# ZTK7628P_convert_board_v1_0.net
KiCad netlist of a schematic drawn in Altium Designer
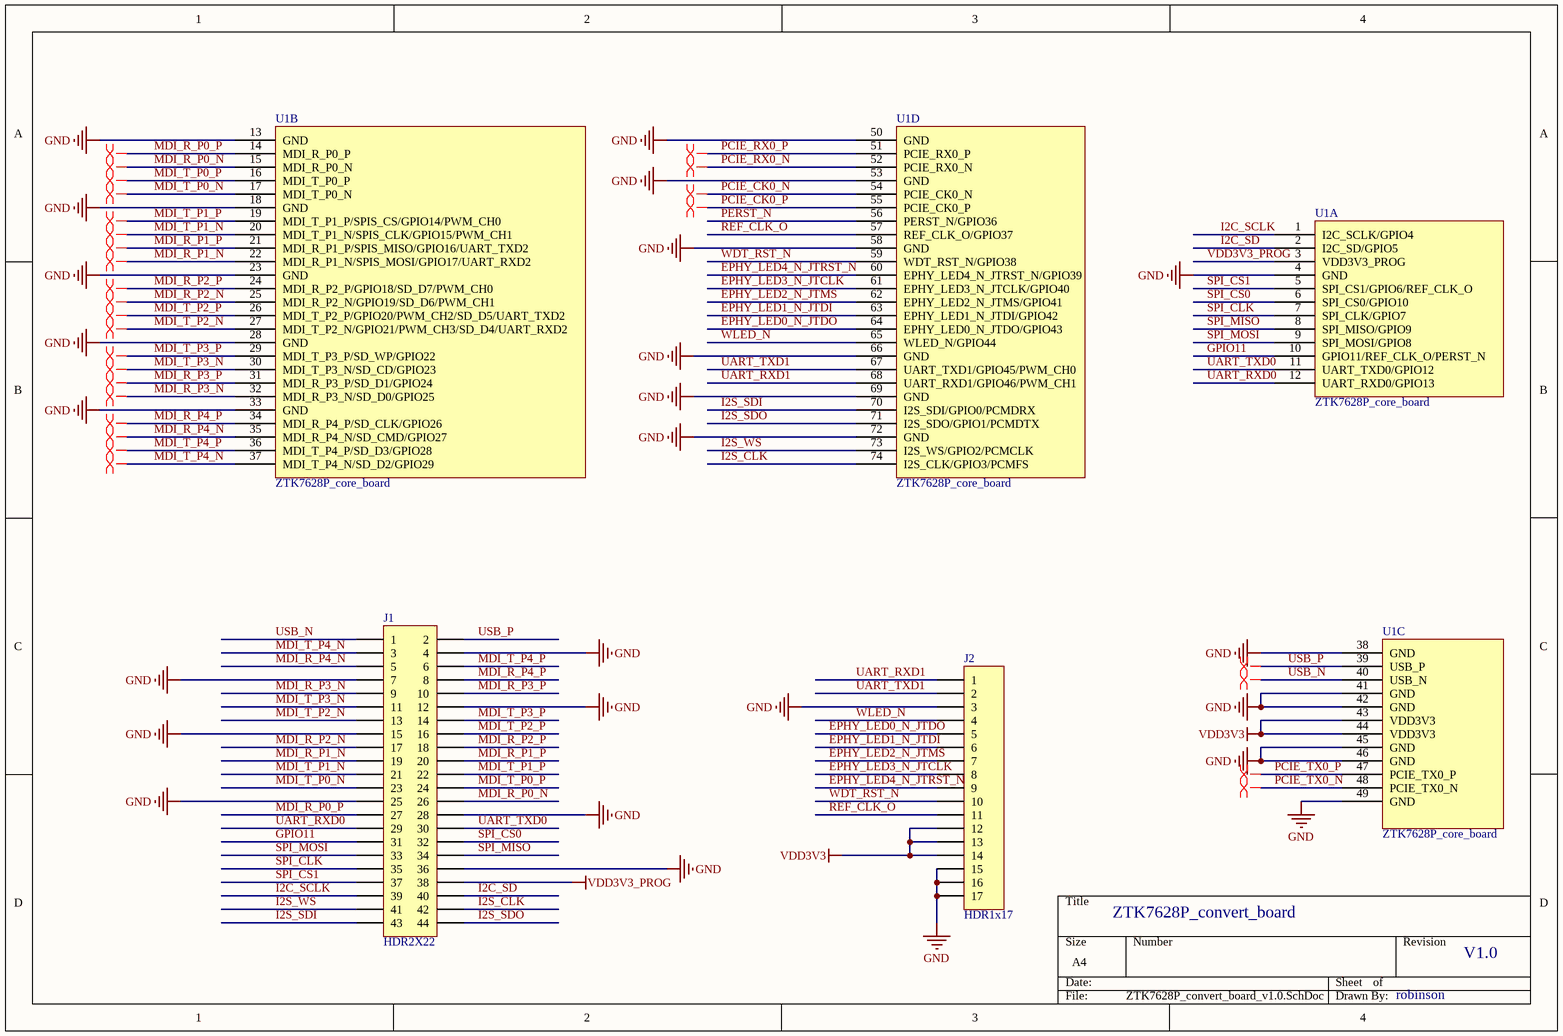
[diagram p0: ZTK7628P_convert_board_v1.0.SchDoc]

(export (version "E")
  (design (tool "Eeschema 10.0.6"))
  (components
    (comp (ref "J1")
      (value "HDR2X22")
      (footprint "MyMiscellaneousConnector:HDR2x22-P-2.0mm")
      (libsource (lib "MyMiscellaneousConnector") (part "HDR2X22"))
    )
    (comp (ref "J2")
      (value "HDR1x17")
      (footprint "MyMiscellaneousConnector:HDR1x17-P-2.0mm")
      (libsource (lib "MyMiscellaneousConnector") (part "HDR1x17"))
    )
    (comp (ref "U1")
      (value "ZTK7628P_core_board")
      (footprint "ZTK7628P_core_board")
      (libsource (lib "MyMiscellaneousDevice") (part "ZTK7628P_core_board"))
    )
  )
  (nets
    (net (code "1") (name "/EPHY_LED0_N_JTDO") (class "Default")
      (node (ref "J2") (pin "5") (pinfunction "5_5") (pintype "passive"))
      (node (ref "U1") (pin "64") (pinfunction "EPHY_LED0_N_JTDO/GPIO43_64") (pintype "passive"))
    )
    (net (code "2") (name "/EPHY_LED1_N_JTDI") (class "Default")
      (node (ref "J2") (pin "6") (pinfunction "6_6") (pintype "passive"))
      (node (ref "U1") (pin "63") (pinfunction "EPHY_LED1_N_JTDI/GPIO42_63") (pintype "passive"))
    )
    (net (code "3") (name "/EPHY_LED2_N_JTMS") (class "Default")
      (node (ref "J2") (pin "7") (pinfunction "7_7") (pintype "passive"))
      (node (ref "U1") (pin "62") (pinfunction "EPHY_LED2_N_JTMS/GPIO41_62") (pintype "passive"))
    )
    (net (code "4") (name "/EPHY_LED3_N_JTCLK") (class "Default")
      (node (ref "J2") (pin "8") (pinfunction "8_8") (pintype "passive"))
      (node (ref "U1") (pin "61") (pinfunction "EPHY_LED3_N_JTCLK/GPIO40_61") (pintype "passive"))
    )
    (net (code "5") (name "/EPHY_LED4_N_JTRST_N") (class "Default")
      (node (ref "J2") (pin "9") (pinfunction "9_9") (pintype "passive"))
      (node (ref "U1") (pin "60") (pinfunction "EPHY_LED4_N_JTRST_N/GPIO39_60") (pintype "passive"))
    )
    (net (code "6") (name "/GPIO11") (class "Default")
      (node (ref "J1") (pin "31") (pinfunction "31_31") (pintype "passive"))
      (node (ref "U1") (pin "10") (pinfunction "GPIO11/REF_CLK_O/PERST_N_10") (pintype "passive"))
    )
    (net (code "7") (name "/I2C_SCLK") (class "Default")
      (node (ref "J1") (pin "39") (pinfunction "39_39") (pintype "passive"))
      (node (ref "U1") (pin "1") (pinfunction "I2C_SCLK/GPIO4_1") (pintype "passive"))
    )
    (net (code "8") (name "/I2C_SD") (class "Default")
      (node (ref "J1") (pin "40") (pinfunction "40_40") (pintype "passive"))
      (node (ref "U1") (pin "2") (pinfunction "I2C_SD/GPIO5_2") (pintype "passive"))
    )
    (net (code "9") (name "/I2S_CLK") (class "Default")
      (node (ref "J1") (pin "42") (pinfunction "42_42") (pintype "passive"))
      (node (ref "U1") (pin "74") (pinfunction "I2S_CLK/GPIO3/PCMFS_74") (pintype "passive"))
    )
    (net (code "10") (name "/I2S_SDI") (class "Default")
      (node (ref "J1") (pin "43") (pinfunction "43_43") (pintype "passive"))
      (node (ref "U1") (pin "70") (pinfunction "I2S_SDI/GPIO0/PCMDRX_70") (pintype "passive"))
    )
    (net (code "11") (name "/I2S_SDO") (class "Default")
      (node (ref "J1") (pin "44") (pinfunction "44_44") (pintype "passive"))
      (node (ref "U1") (pin "71") (pinfunction "I2S_SDO/GPIO1/PCMDTX_71") (pintype "passive"))
    )
    (net (code "12") (name "/I2S_WS") (class "Default")
      (node (ref "J1") (pin "41") (pinfunction "41_41") (pintype "passive"))
      (node (ref "U1") (pin "73") (pinfunction "I2S_WS/GPIO2/PCMCLK_73") (pintype "passive"))
    )
    (net (code "13") (name "/MDI_R_P0_N") (class "Default")
      (node (ref "J1") (pin "26") (pinfunction "26_26") (pintype "passive"))
      (node (ref "U1") (pin "15") (pinfunction "MDI_R_P0_N_15") (pintype "passive"))
    )
    (net (code "14") (name "/MDI_R_P0_P") (class "Default")
      (node (ref "J1") (pin "27") (pinfunction "27_27") (pintype "passive"))
      (node (ref "U1") (pin "14") (pinfunction "MDI_R_P0_P_14") (pintype "passive"))
    )
    (net (code "15") (name "/MDI_R_P1_N") (class "Default")
      (node (ref "J1") (pin "19") (pinfunction "19_19") (pintype "passive"))
      (node (ref "U1") (pin "22") (pinfunction "MDI_R_P1_N/SPIS_MOSI/GPIO17/UART_RXD2_22") (pintype "passive"))
    )
    (net (code "16") (name "/MDI_R_P1_P") (class "Default")
      (node (ref "J1") (pin "20") (pinfunction "20_20") (pintype "passive"))
      (node (ref "U1") (pin "21") (pinfunction "MDI_R_P1_P/SPIS_MISO/GPIO16/UART_TXD2_21") (pintype "passive"))
    )
    (net (code "17") (name "/MDI_R_P2_N") (class "Default")
      (node (ref "J1") (pin "17") (pinfunction "17_17") (pintype "passive"))
      (node (ref "U1") (pin "25") (pinfunction "MDI_R_P2_N/GPIO19/SD_D6/PWM_CH1_25") (pintype "passive"))
    )
    (net (code "18") (name "/MDI_R_P2_P") (class "Default")
      (node (ref "J1") (pin "18") (pinfunction "18_18") (pintype "passive"))
      (node (ref "U1") (pin "24") (pinfunction "MDI_R_P2_P/GPIO18/SD_D7/PWM_CH0_24") (pintype "passive"))
    )
    (net (code "19") (name "/MDI_R_P3_N") (class "Default")
      (node (ref "J1") (pin "9") (pinfunction "9_9") (pintype "passive"))
      (node (ref "U1") (pin "32") (pinfunction "MDI_R_P3_N/SD_D0/GPIO25_32") (pintype "passive"))
    )
    (net (code "20") (name "/MDI_R_P3_P") (class "Default")
      (node (ref "J1") (pin "10") (pinfunction "10_10") (pintype "passive"))
      (node (ref "U1") (pin "31") (pinfunction "MDI_R_P3_P/SD_D1/GPIO24_31") (pintype "passive"))
    )
    (net (code "21") (name "/MDI_R_P4_N") (class "Default")
      (node (ref "J1") (pin "5") (pinfunction "5_5") (pintype "passive"))
      (node (ref "U1") (pin "35") (pinfunction "MDI_R_P4_N/SD_CMD/GPIO27_35") (pintype "passive"))
    )
    (net (code "22") (name "/MDI_R_P4_P") (class "Default")
      (node (ref "J1") (pin "8") (pinfunction "8_8") (pintype "passive"))
      (node (ref "U1") (pin "34") (pinfunction "MDI_R_P4_P/SD_CLK/GPIO26_34") (pintype "passive"))
    )
    (net (code "23") (name "/MDI_T_P0_N") (class "Default")
      (node (ref "J1") (pin "23") (pinfunction "23_23") (pintype "passive"))
      (node (ref "U1") (pin "17") (pinfunction "MDI_T_P0_N_17") (pintype "passive"))
    )
    (net (code "24") (name "/MDI_T_P0_P") (class "Default")
      (node (ref "J1") (pin "24") (pinfunction "24_24") (pintype "passive"))
      (node (ref "U1") (pin "16") (pinfunction "MDI_T_P0_P_16") (pintype "passive"))
    )
    (net (code "25") (name "/MDI_T_P1_N") (class "Default")
      (node (ref "J1") (pin "21") (pinfunction "21_21") (pintype "passive"))
      (node (ref "U1") (pin "20") (pinfunction "MDI_T_P1_N/SPIS_CLK/GPIO15/PWM_CH1_20") (pintype "passive"))
    )
    (net (code "26") (name "/MDI_T_P1_P") (class "Default")
      (node (ref "J1") (pin "22") (pinfunction "22_22") (pintype "passive"))
      (node (ref "U1") (pin "19") (pinfunction "MDI_T_P1_P/SPIS_CS/GPIO14/PWM_CH0_19") (pintype "passive"))
    )
    (net (code "27") (name "/MDI_T_P2_N") (class "Default")
      (node (ref "J1") (pin "13") (pinfunction "13_13") (pintype "passive"))
      (node (ref "U1") (pin "27") (pinfunction "MDI_T_P2_N/GPIO21/PWM_CH3/SD_D4/UART_RXD2_27") (pintype "passive"))
    )
    (net (code "28") (name "/MDI_T_P2_P") (class "Default")
      (node (ref "J1") (pin "16") (pinfunction "16_16") (pintype "passive"))
      (node (ref "U1") (pin "26") (pinfunction "MDI_T_P2_P/GPIO20/PWM_CH2/SD_D5/UART_TXD2_26") (pintype "passive"))
    )
    (net (code "29") (name "/MDI_T_P3_N") (class "Default")
      (node (ref "J1") (pin "11") (pinfunction "11_11") (pintype "passive"))
      (node (ref "U1") (pin "30") (pinfunction "MDI_T_P3_N/SD_CD/GPIO23_30") (pintype "passive"))
    )
    (net (code "30") (name "/MDI_T_P3_P") (class "Default")
      (node (ref "J1") (pin "14") (pinfunction "14_14") (pintype "passive"))
      (node (ref "U1") (pin "29") (pinfunction "MDI_T_P3_P/SD_WP/GPIO22_29") (pintype "passive"))
    )
    (net (code "31") (name "/MDI_T_P4_N") (class "Default")
      (node (ref "J1") (pin "3") (pinfunction "3_3") (pintype "passive"))
      (node (ref "U1") (pin "37") (pinfunction "MDI_T_P4_N/SD_D2/GPIO29_37") (pintype "passive"))
    )
    (net (code "32") (name "/MDI_T_P4_P") (class "Default")
      (node (ref "J1") (pin "6") (pinfunction "6_6") (pintype "passive"))
      (node (ref "U1") (pin "36") (pinfunction "MDI_T_P4_P/SD_D3/GPIO28_36") (pintype "passive"))
    )
    (net (code "33") (name "/PCIE_CK0_N") (class "Default")
      (node (ref "U1") (pin "54") (pinfunction "PCIE_CK0_N_54") (pintype "passive"))
    )
    (net (code "34") (name "/PCIE_CK0_P") (class "Default")
      (node (ref "U1") (pin "55") (pinfunction "PCIE_CK0_P_55") (pintype "passive"))
    )
    (net (code "35") (name "/PCIE_RX0_N") (class "Default")
      (node (ref "U1") (pin "52") (pinfunction "PCIE_RX0_N_52") (pintype "passive"))
    )
    (net (code "36") (name "/PCIE_RX0_P") (class "Default")
      (node (ref "U1") (pin "51") (pinfunction "PCIE_RX0_P_51") (pintype "passive"))
    )
    (net (code "37") (name "/PCIE_TX0_N") (class "Default")
      (node (ref "U1") (pin "48") (pinfunction "PCIE_TX0_N_48") (pintype "passive"))
    )
    (net (code "38") (name "/PCIE_TX0_P") (class "Default")
      (node (ref "U1") (pin "47") (pinfunction "PCIE_TX0_P_47") (pintype "passive"))
    )
    (net (code "39") (name "/PERST_N") (class "Default")
      (node (ref "U1") (pin "56") (pinfunction "PERST_N/GPIO36_56") (pintype "passive"))
    )
    (net (code "40") (name "/REF_CLK_O") (class "Default")
      (node (ref "J2") (pin "11") (pinfunction "11_11") (pintype "passive"))
      (node (ref "U1") (pin "57") (pinfunction "REF_CLK_O/GPIO37_57") (pintype "passive"))
    )
    (net (code "41") (name "/SPI_CLK") (class "Default")
      (node (ref "J1") (pin "35") (pinfunction "35_35") (pintype "passive"))
      (node (ref "U1") (pin "7") (pinfunction "SPI_CLK/GPIO7_7") (pintype "passive"))
    )
    (net (code "42") (name "/SPI_CS0") (class "Default")
      (node (ref "J1") (pin "32") (pinfunction "32_32") (pintype "passive"))
      (node (ref "U1") (pin "6") (pinfunction "SPI_CS0/GPIO10_6") (pintype "passive"))
    )
    (net (code "43") (name "/SPI_CS1") (class "Default")
      (node (ref "J1") (pin "37") (pinfunction "37_37") (pintype "passive"))
      (node (ref "U1") (pin "5") (pinfunction "SPI_CS1/GPIO6/REF_CLK_O_5") (pintype "passive"))
    )
    (net (code "44") (name "/SPI_MISO") (class "Default")
      (node (ref "J1") (pin "34") (pinfunction "34_34") (pintype "passive"))
      (node (ref "U1") (pin "8") (pinfunction "SPI_MISO/GPIO9_8") (pintype "passive"))
    )
    (net (code "45") (name "/SPI_MOSI") (class "Default")
      (node (ref "J1") (pin "33") (pinfunction "33_33") (pintype "passive"))
      (node (ref "U1") (pin "9") (pinfunction "SPI_MOSI/GPIO8_9") (pintype "passive"))
    )
    (net (code "46") (name "/UART_RXD0") (class "Default")
      (node (ref "J1") (pin "29") (pinfunction "29_29") (pintype "passive"))
      (node (ref "U1") (pin "12") (pinfunction "UART_RXD0/GPIO13_12") (pintype "passive"))
    )
    (net (code "47") (name "/UART_RXD1") (class "Default")
      (node (ref "J2") (pin "1") (pinfunction "1_1") (pintype "passive"))
      (node (ref "U1") (pin "68") (pinfunction "UART_RXD1/GPIO46/PWM_CH1_68") (pintype "passive"))
    )
    (net (code "48") (name "/UART_TXD0") (class "Default")
      (node (ref "J1") (pin "30") (pinfunction "30_30") (pintype "passive"))
      (node (ref "U1") (pin "11") (pinfunction "UART_TXD0/GPIO12_11") (pintype "passive"))
    )
    (net (code "49") (name "/UART_TXD1") (class "Default")
      (node (ref "J2") (pin "2") (pinfunction "2_2") (pintype "passive"))
      (node (ref "U1") (pin "67") (pinfunction "UART_TXD1/GPIO45/PWM_CH0_67") (pintype "passive"))
    )
    (net (code "50") (name "/USB_N") (class "Default")
      (node (ref "J1") (pin "1") (pinfunction "1_1") (pintype "passive"))
      (node (ref "U1") (pin "40") (pinfunction "USB_N_40") (pintype "passive"))
    )
    (net (code "51") (name "/USB_P") (class "Default")
      (node (ref "J1") (pin "2") (pinfunction "2_2") (pintype "passive"))
      (node (ref "U1") (pin "39") (pinfunction "USB_P_39") (pintype "passive"))
    )
    (net (code "52") (name "/WDT_RST_N") (class "Default")
      (node (ref "J2") (pin "10") (pinfunction "10_10") (pintype "passive"))
      (node (ref "U1") (pin "59") (pinfunction "WDT_RST_N/GPIO38_59") (pintype "passive"))
    )
    (net (code "53") (name "/WLED_N") (class "Default")
      (node (ref "J2") (pin "4") (pinfunction "4_4") (pintype "passive"))
      (node (ref "U1") (pin "65") (pinfunction "WLED_N/GPIO44_65") (pintype "passive"))
    )
    (net (code "54") (name "GND") (class "Default")
      (node (ref "J1") (pin "12") (pinfunction "12_12") (pintype "passive"))
      (node (ref "J1") (pin "15") (pinfunction "15_15") (pintype "passive"))
      (node (ref "J1") (pin "25") (pinfunction "25_25") (pintype "passive"))
      (node (ref "J1") (pin "28") (pinfunction "28_28") (pintype "passive"))
      (node (ref "J1") (pin "36") (pinfunction "36_36") (pintype "passive"))
      (node (ref "J1") (pin "4") (pinfunction "4_4") (pintype "passive"))
      (node (ref "J1") (pin "7") (pinfunction "7_7") (pintype "passive"))
      (node (ref "J2") (pin "15") (pinfunction "15_15") (pintype "passive"))
      (node (ref "J2") (pin "16") (pinfunction "16_16") (pintype "passive"))
      (node (ref "J2") (pin "17") (pinfunction "17_17") (pintype "passive"))
      (node (ref "J2") (pin "3") (pinfunction "3_3") (pintype "passive"))
      (node (ref "U1") (pin "13") (pinfunction "GND_13") (pintype "passive"))
      (node (ref "U1") (pin "18") (pinfunction "GND_18") (pintype "passive"))
      (node (ref "U1") (pin "23") (pinfunction "GND_23") (pintype "passive"))
      (node (ref "U1") (pin "28") (pinfunction "GND_28") (pintype "passive"))
      (node (ref "U1") (pin "33") (pinfunction "GND_33") (pintype "passive"))
      (node (ref "U1") (pin "38") (pinfunction "GND_38") (pintype "passive"))
      (node (ref "U1") (pin "4") (pinfunction "GND_4") (pintype "passive"))
      (node (ref "U1") (pin "41") (pinfunction "GND_41") (pintype "passive"))
      (node (ref "U1") (pin "42") (pinfunction "GND_42") (pintype "passive"))
      (node (ref "U1") (pin "45") (pinfunction "GND_45") (pintype "passive"))
      (node (ref "U1") (pin "46") (pinfunction "GND_46") (pintype "passive"))
      (node (ref "U1") (pin "49") (pinfunction "GND_49") (pintype "passive"))
      (node (ref "U1") (pin "50") (pinfunction "GND_50") (pintype "passive"))
      (node (ref "U1") (pin "53") (pinfunction "GND_53") (pintype "passive"))
      (node (ref "U1") (pin "58") (pinfunction "GND_58") (pintype "passive"))
      (node (ref "U1") (pin "66") (pinfunction "GND_66") (pintype "passive"))
      (node (ref "U1") (pin "69") (pinfunction "GND_69") (pintype "passive"))
      (node (ref "U1") (pin "72") (pinfunction "GND_72") (pintype "passive"))
    )
    (net (code "55") (name "VDD3V3") (class "Default")
      (node (ref "J2") (pin "12") (pinfunction "12_12") (pintype "passive"))
      (node (ref "J2") (pin "13") (pinfunction "13_13") (pintype "passive"))
      (node (ref "J2") (pin "14") (pinfunction "14_14") (pintype "passive"))
      (node (ref "U1") (pin "43") (pinfunction "VDD3V3_43") (pintype "passive"))
      (node (ref "U1") (pin "44") (pinfunction "VDD3V3_44") (pintype "passive"))
    )
    (net (code "56") (name "VDD3V3_PROG") (class "Default")
      (node (ref "J1") (pin "38") (pinfunction "38_38") (pintype "passive"))
      (node (ref "U1") (pin "3") (pinfunction "VDD3V3_PROG_3") (pintype "passive"))
    )
  )
)
